# Power.net
KiCad netlist of a schematic drawn in Altium Designer
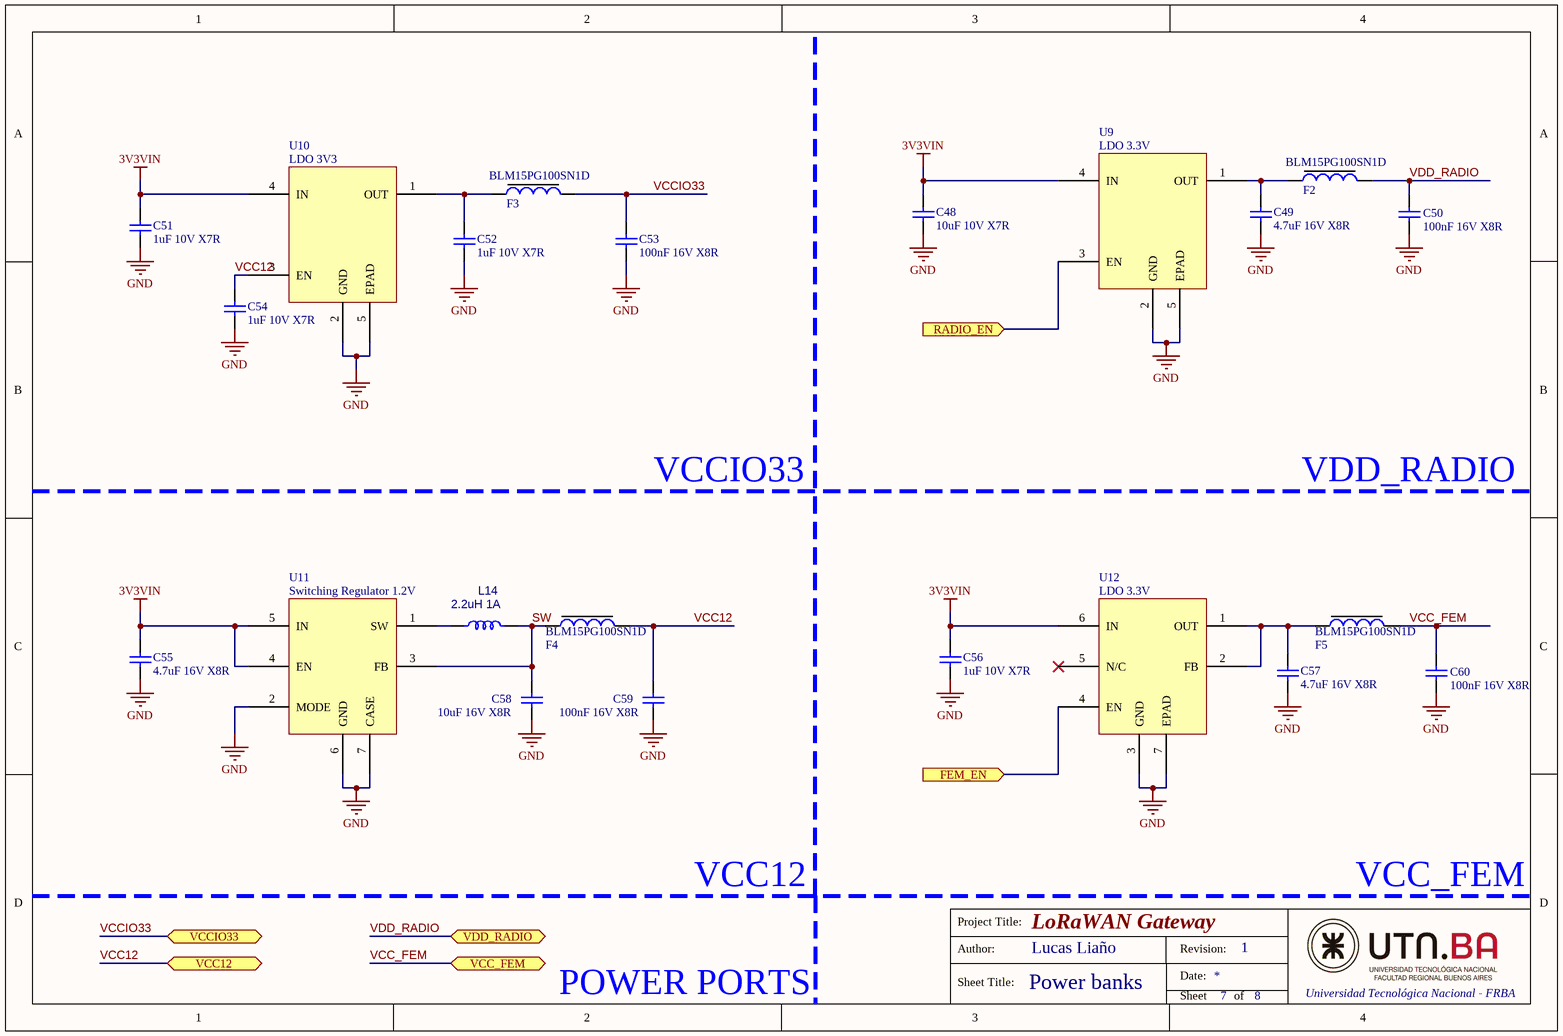
[diagram p0: Power.SchDoc]

(export (version "E")
  (design (tool "Eeschema 10.0.6"))
  (components
    (comp (ref "C48")
      (value "10uF 10V X7R")
      (footprint "C_0603")
      (description "Capacitor")
      (fields (field (name "MPN") "C2012X7R1A106K125AC") (field (name "MANUFACTURER") "TDK Corportation"))
      (libsource (lib "lorawan_gateway") (part "Cap"))
    )
    (comp (ref "C49")
      (value "4.7uF 16V X8R")
      (footprint "C_0603")
      (description "Capacitor")
      (fields (field (name "MPN") "CGA5L3X8R1C475M160AB") (field (name "MANUFACTURER") "TDK Corporation"))
      (libsource (lib "lorawan_gateway") (part "Cap"))
    )
    (comp (ref "C50")
      (value "100nF 16V X8R")
      (footprint "C_0603")
      (description "Capacitor")
      (fields (field (name "MPN") "C1206C104K4HACAUTO") (field (name "MANUFACTURER") "KEMET"))
      (libsource (lib "lorawan_gateway") (part "Cap"))
    )
    (comp (ref "C51")
      (value "1uF 10V X7R")
      (footprint "C_0603")
      (description "Capacitor")
      (fields (field (name "MPN") "C0603C105K8RAC7867") (field (name "MANUFACTURER") "KEMET"))
      (libsource (lib "lorawan_gateway") (part "Cap"))
    )
    (comp (ref "C52")
      (value "1uF 10V X7R")
      (footprint "C_0603")
      (description "Capacitor")
      (fields (field (name "MPN") "C0603C105K8RAC7867") (field (name "MANUFACTURER") "KEMET"))
      (libsource (lib "lorawan_gateway") (part "Cap"))
    )
    (comp (ref "C53")
      (value "100nF 16V X8R")
      (footprint "C_0603")
      (description "Capacitor")
      (fields (field (name "MPN") "C1206C104K4HACAUTO") (field (name "MANUFACTURER") "KEMET"))
      (libsource (lib "lorawan_gateway") (part "Cap"))
    )
    (comp (ref "C54")
      (value "1uF 10V X7R")
      (footprint "C_0603")
      (description "Capacitor")
      (fields (field (name "MPN") "C0603C105K8RAC7867") (field (name "MANUFACTURER") "KEMET"))
      (libsource (lib "lorawan_gateway") (part "Cap"))
    )
    (comp (ref "C55")
      (value "4.7uF 16V X8R")
      (footprint "C_0603")
      (description "Capacitor")
      (fields (field (name "MPN") "CGA5L3X8R1C475M160AB") (field (name "MANUFACTURER") "TDK Corporation"))
      (libsource (lib "lorawan_gateway") (part "Cap"))
    )
    (comp (ref "C56")
      (value "1uF 10V X7R")
      (footprint "C_0603")
      (description "Capacitor")
      (fields (field (name "MPN") "C0603C105K8RAC7867") (field (name "MANUFACTURER") "KEMET"))
      (libsource (lib "lorawan_gateway") (part "Cap"))
    )
    (comp (ref "C57")
      (value "4.7uF 16V X8R")
      (footprint "C_0603")
      (description "Capacitor")
      (fields (field (name "MPN") "CGA5L3X8R1C475M160AB") (field (name "MANUFACTURER") "TDK Corporation"))
      (libsource (lib "lorawan_gateway") (part "Cap"))
    )
    (comp (ref "C58")
      (value "10uF 16V X8R")
      (footprint "C_0603")
      (description "Capacitor")
      (fields (field (name "MPN") "CGA6P3X8R1C106M250AB") (field (name "MANUFACTURER") "TDK Corporation"))
      (libsource (lib "lorawan_gateway") (part "Cap"))
    )
    (comp (ref "C59")
      (value "100nF 16V X8R")
      (footprint "C_0603")
      (description "Capacitor")
      (fields (field (name "MPN") "C1206C104K4HACAUTO") (field (name "MANUFACTURER") "KEMET"))
      (libsource (lib "lorawan_gateway") (part "Cap"))
    )
    (comp (ref "C60")
      (value "100nF 16V X8R")
      (footprint "C_0603")
      (description "Capacitor")
      (fields (field (name "MPN") "C1206C104K4HACAUTO") (field (name "MANUFACTURER") "KEMET"))
      (libsource (lib "lorawan_gateway") (part "Cap"))
    )
    (comp (ref "F2")
      (value "BLM15PG100SN1D")
      (footprint "L_0402")
      (description "Ferrite bead 10 ohm 1A")
      (fields (field (name "MANUFACTURER") "Murata Electronics"))
      (libsource (lib "lorawan_gateway") (part "Ferrite beads"))
    )
    (comp (ref "F3")
      (value "BLM15PG100SN1D")
      (footprint "L_0402")
      (description "Ferrite bead 10 ohm 1A")
      (fields (field (name "MANUFACTURER") "Murata Electronics"))
      (libsource (lib "lorawan_gateway") (part "Ferrite beads"))
    )
    (comp (ref "F4")
      (value "BLM15PG100SN1D")
      (footprint "L_0402")
      (description "Ferrite bead 10 ohm 1A")
      (fields (field (name "MANUFACTURER") "Murata Electronics"))
      (libsource (lib "lorawan_gateway") (part "Ferrite beads"))
    )
    (comp (ref "F5")
      (value "BLM15PG100SN1D")
      (footprint "L_0402")
      (description "Ferrite bead 10 ohm 1A")
      (fields (field (name "MANUFACTURER") "Murata Electronics"))
      (libsource (lib "lorawan_gateway") (part "Ferrite beads"))
    )
    (comp (ref "L14")
      (value "2.2uH 1A")
      (footprint "L_1008")
      (description "FIXED IND 2.2UH 1A 150 MOHM")
      (fields (field (name "MANUFACTURER") "Murata Electronics") (field (name "MPN") "LQM2HPN2R2MJ0L"))
      (libsource (lib "lorawan_gateway") (part "IND"))
    )
    (comp (ref "U9")
      (value "LDO 3.3V")
      (footprint "UDFN4_1x1mm")
      (description "LDO IC Positive Fixed 1 Output 300mA 4-UDFN (1.0x1.0)")
      (fields (field (name "MANUFACTURER") "onsemi") (field (name "MPN") "NCP114AMX330TBG"))
      (libsource (lib "lorawan_gateway") (part "NCP114"))
    )
    (comp (ref "U10")
      (value "LDO 3V3")
      (footprint "UDFN4_1x1mm")
      (description "LDO IC Positive Fixed 1 Output 150mA 4-UDFN")
      (fields (field (name "MANUFACTURER") "onsemi") (field (name "MPN") "NCP103AMX300TCG"))
      (libsource (lib "lorawan_gateway") (part "NCP103"))
    )
    (comp (ref "U11")
      (value "Switching Regulator 1.2V")
      (footprint "WSON-6")
      (description "Switching Regulator IC Positive Fixed 1.2V 1 Output 300mA 6-WDFN")
      (fields (field (name "MANUFACTURER") "Texas Instruments") (field (name "MPN") "TPS62242DRVT"))
      (libsource (lib "lorawan_gateway") (part "TPS62242DRV"))
    )
    (comp (ref "U12")
      (value "LDO 3.3V")
      (footprint "XDFN6_1.2X1.2mm")
      (description "LDO IC Positive Fixed 1 Output 500mA 6-XDFN (1.2x1.2)")
      (fields (field (name "MANUFACTURER") "onsemi") (field (name "MPN") "NCP176BMX330TCG"))
      (libsource (lib "lorawan_gateway") (part "NCP176BMX330TCG"))
    )
  )
  (nets
    (net (code "1") (name "/FEM_EN") (class "Default")
      (node (ref "U12") (pin "4") (pinfunction "EN_4") (pintype "passive"))
    )
    (net (code "2") (name "/RADIO_EN") (class "Default")
      (node (ref "U9") (pin "3") (pinfunction "EN_3") (pintype "passive"))
    )
    (net (code "3") (name "/SW") (class "Default")
      (node (ref "C58") (pin "1") (pinfunction "1_1") (pintype "passive"))
      (node (ref "F4") (pin "1") (pinfunction "1_1") (pintype "passive"))
      (node (ref "L14") (pin "2") (pinfunction "2_2") (pintype "passive"))
      (node (ref "U11") (pin "3") (pinfunction "FB_3") (pintype "passive"))
    )
    (net (code "4") (name "/VCC12") (class "Default")
      (node (ref "C54") (pin "2") (pinfunction "2_2") (pintype "passive"))
      (node (ref "C59") (pin "1") (pinfunction "1_1") (pintype "passive"))
      (node (ref "F4") (pin "2") (pinfunction "2_2") (pintype "passive"))
      (node (ref "U10") (pin "3") (pinfunction "EN_3") (pintype "passive"))
    )
    (net (code "5") (name "/VCCIO33") (class "Default")
      (node (ref "C53") (pin "2") (pinfunction "2_2") (pintype "passive"))
      (node (ref "F3") (pin "2") (pinfunction "2_2") (pintype "passive"))
    )
    (net (code "6") (name "/VCC_FEM") (class "Default")
      (node (ref "C60") (pin "1") (pinfunction "1_1") (pintype "passive"))
      (node (ref "F5") (pin "2") (pinfunction "2_2") (pintype "passive"))
    )
    (net (code "7") (name "/VDD_RADIO") (class "Default")
      (node (ref "C50") (pin "1") (pinfunction "1_1") (pintype "passive"))
      (node (ref "F2") (pin "2") (pinfunction "2_2") (pintype "passive"))
    )
    (net (code "8") (name "3V3VIN") (class "Default")
      (node (ref "C48") (pin "1") (pinfunction "1_1") (pintype "passive"))
      (node (ref "C51") (pin "1") (pinfunction "1_1") (pintype "passive"))
      (node (ref "C55") (pin "1") (pinfunction "1_1") (pintype "passive"))
      (node (ref "C56") (pin "1") (pinfunction "1_1") (pintype "passive"))
      (node (ref "U10") (pin "4") (pinfunction "IN_4") (pintype "passive"))
      (node (ref "U11") (pin "4") (pinfunction "EN_4") (pintype "passive"))
      (node (ref "U11") (pin "5") (pinfunction "IN_5") (pintype "passive"))
      (node (ref "U12") (pin "6") (pinfunction "IN_6") (pintype "passive"))
      (node (ref "U9") (pin "4") (pinfunction "IN_4") (pintype "passive"))
    )
    (net (code "9") (name "GND") (class "Default")
      (node (ref "C48") (pin "2") (pinfunction "2_2") (pintype "passive"))
      (node (ref "C49") (pin "2") (pinfunction "2_2") (pintype "passive"))
      (node (ref "C50") (pin "2") (pinfunction "2_2") (pintype "passive"))
      (node (ref "C51") (pin "2") (pinfunction "2_2") (pintype "passive"))
      (node (ref "C52") (pin "2") (pinfunction "2_2") (pintype "passive"))
      (node (ref "C53") (pin "1") (pinfunction "1_1") (pintype "passive"))
      (node (ref "C54") (pin "1") (pinfunction "1_1") (pintype "passive"))
      (node (ref "C55") (pin "2") (pinfunction "2_2") (pintype "passive"))
      (node (ref "C56") (pin "2") (pinfunction "2_2") (pintype "passive"))
      (node (ref "C57") (pin "2") (pinfunction "2_2") (pintype "passive"))
      (node (ref "C58") (pin "2") (pinfunction "2_2") (pintype "passive"))
      (node (ref "C59") (pin "2") (pinfunction "2_2") (pintype "passive"))
      (node (ref "C60") (pin "2") (pinfunction "2_2") (pintype "passive"))
      (node (ref "U10") (pin "2") (pinfunction "GND_2") (pintype "passive"))
      (node (ref "U10") (pin "5") (pinfunction "EPAD_5") (pintype "passive"))
      (node (ref "U11") (pin "2") (pinfunction "MODE_2") (pintype "passive"))
      (node (ref "U11") (pin "6") (pinfunction "GND_6") (pintype "passive"))
      (node (ref "U11") (pin "7") (pinfunction "CASE_7") (pintype "passive"))
      (node (ref "U12") (pin "3") (pinfunction "GND_3") (pintype "passive"))
      (node (ref "U12") (pin "7") (pinfunction "EPAD_7") (pintype "passive"))
      (node (ref "U9") (pin "2") (pinfunction "GND_2") (pintype "passive"))
      (node (ref "U9") (pin "5") (pinfunction "EPAD_5") (pintype "passive"))
    )
    (net (code "10") (name "Net-(U9-OUT)") (class "Default")
      (node (ref "C49") (pin "1") (pinfunction "1_1") (pintype "passive"))
      (node (ref "F2") (pin "1") (pinfunction "1_1") (pintype "passive"))
      (node (ref "U9") (pin "1") (pinfunction "OUT_1") (pintype "passive"))
    )
    (net (code "11") (name "Net-(U10-OUT)") (class "Default")
      (node (ref "C52") (pin "1") (pinfunction "1_1") (pintype "passive"))
      (node (ref "F3") (pin "1") (pinfunction "1_1") (pintype "passive"))
      (node (ref "U10") (pin "1") (pinfunction "OUT_1") (pintype "passive"))
    )
    (net (code "12") (name "Net-(U11-SW)") (class "Default")
      (node (ref "L14") (pin "1") (pinfunction "1_1") (pintype "passive"))
      (node (ref "U11") (pin "1") (pinfunction "SW_1") (pintype "passive"))
    )
    (net (code "13") (name "Net-(U12-FB)") (class "Default")
      (node (ref "C57") (pin "1") (pinfunction "1_1") (pintype "passive"))
      (node (ref "F5") (pin "1") (pinfunction "1_1") (pintype "passive"))
      (node (ref "U12") (pin "1") (pinfunction "OUT_1") (pintype "passive"))
      (node (ref "U12") (pin "2") (pinfunction "FB_2") (pintype "passive"))
    )
    (net (code "14") (name "unconnected-(U12-N{slash}C-Pad5)") (class "Default")
      (node (ref "U12") (pin "5") (pinfunction "N/C_5") (pintype "passive+no_connect"))
    )
  )
)
